# uINS.net
KiCad netlist of a schematic drawn in Altium Designer
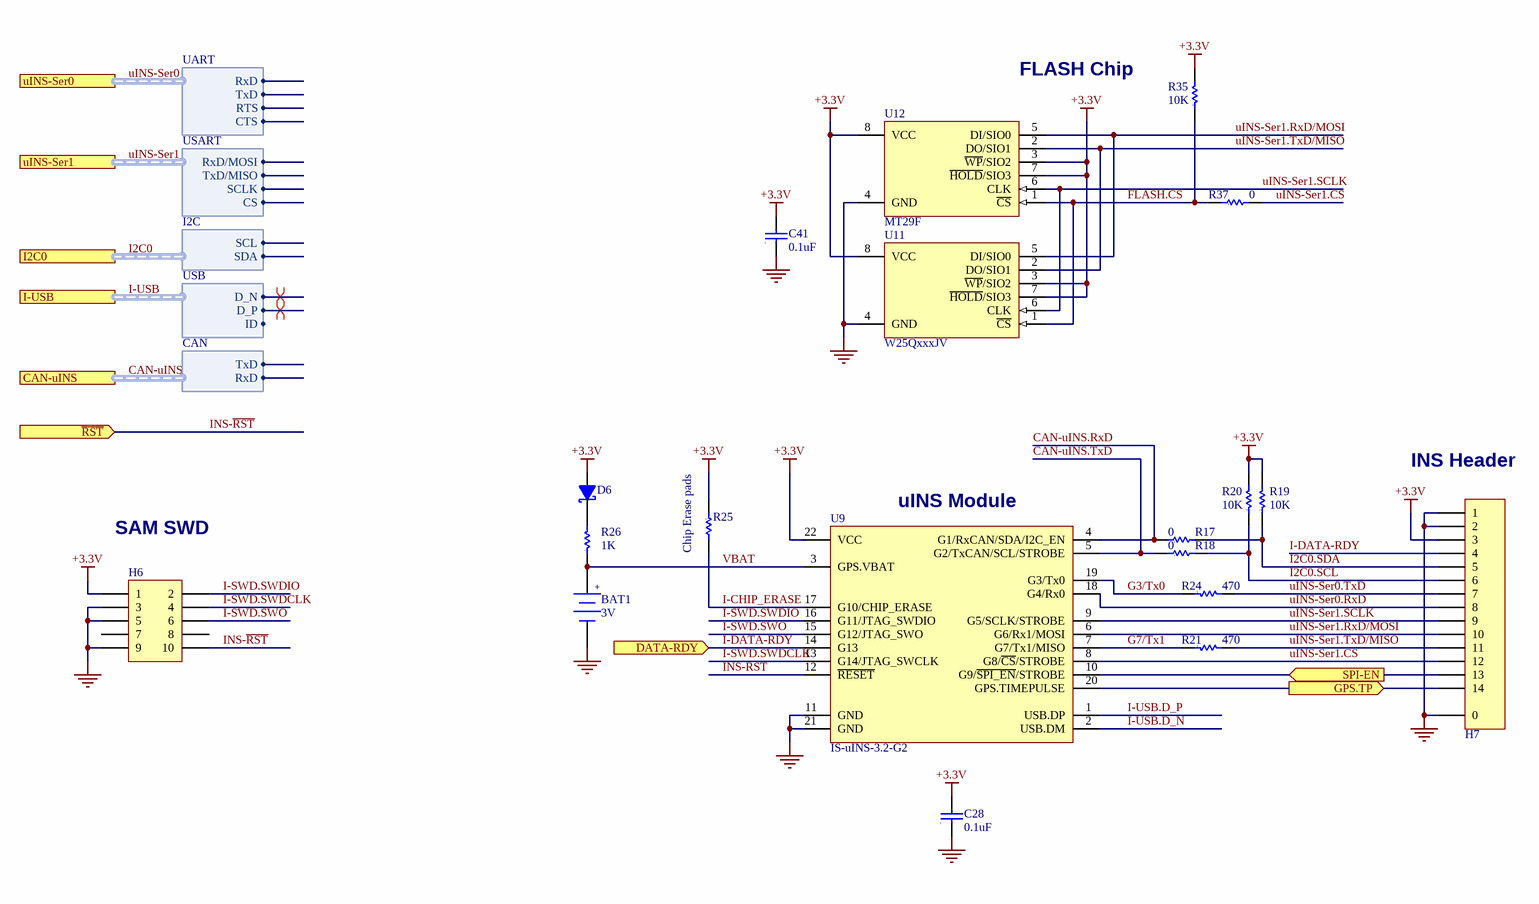
[diagram p0: uINS.SchDoc]

(export (version "E")
  (design (tool "Eeschema 10.0.6"))
  (components
    (comp (ref "BAT1")
      (value "Battery")
      (footprint "ML614S")
      (description "BATTERY LITH 3V 3MAH COIN 6.8MM")
      (fields (field (name "VOLTAGE RATING") "3V"))
      (libsource (lib "General") (part "Battery"))
    )
    (comp (ref "C28")
      (value "0.1uF")
      (footprint "0402")
      (description "CAP CER .10UF 50V X7R 10% 0402")
      (fields
        (field (name "MANUFACTURER") "TDK Corporation")
        (field (name "MANUFACTURER PART NUMBER") "C1005X7R1H104K")
        (field (name "PUBLISHER") "Altium Limited")
      )
      (libsource (lib "General") (part "Cap"))
    )
    (comp (ref "C41")
      (value "0.1uF")
      (footprint "0402")
      (description "CAP CER .10UF 50V X7R 10% 0402")
      (fields
        (field (name "MANUFACTURER") "TDK Corporation")
        (field (name "MANUFACTURER PART NUMBER") "C1005X7R1H104K")
        (field (name "PUBLISHER") "Altium Limited")
      )
      (libsource (lib "General") (part "Cap"))
    )
    (comp (ref "D6")
      (value "Diode - Schottky")
      (footprint "D0603B")
      (description "DIODE SCHOTTKY 30V 2A 0603")
      (fields
        (field (name "MANUFACTURER") "Vishay")
        (field (name "MANUFACTURER PART NUMBER") "VSKY20301608-G4-08")
      )
      (libsource (lib "General") (part "Diode - Schottky"))
    )
    (comp (ref "H6")
      (value "Hdr - 5x2pin")
      (footprint "FTSH-105-01-L-DV-K-A-P")
      (description "CONN HEADER 10POS DUAL .05\" SMD")
      (fields
        (field (name "MANUFACTURER") "Samtec")
        (field (name "MANUFACTURER PART NUMBER") "FTSH-105-01-L-DV-K-A-P")
      )
      (libsource (lib "Connectors") (part "Hdr - 5x2pin"))
    )
    (comp (ref "H7")
      (value "Hdr - 14pin - mount")
      (footprint "SM14B-GHS-TB(LF)(SN)")
      (description "CONN HEADER GH SIDE 14POS 1.25MM")
      (fields
        (field (name "MANUFACTURER") "JST")
        (field (name "MANUFACTURER PART NUMBER") "SM14B-GHS-TB(LF)(SN)")
      )
      (libsource (lib "Connectors") (part "Hdr - 14pin - mount"))
    )
    (comp (ref "R17")
      (value "0")
      (footprint "R0402")
      (description "RES SMD 0 OHM JUMPER 1/16W 0402")
      (fields
        (field (name "MANUFACTURER") "Yageo")
        (field (name "MANUFACTURER PART NUMBER") "RC0402JR-070RL")
      )
      (libsource (lib "") (part "Res_1"))
    )
    (comp (ref "R18")
      (value "0")
      (footprint "R0402")
      (description "RES SMD 0 OHM JUMPER 1/16W 0402")
      (fields
        (field (name "MANUFACTURER") "Yageo")
        (field (name "MANUFACTURER PART NUMBER") "RC0402JR-070RL")
      )
      (libsource (lib "") (part "Res_1"))
    )
    (comp (ref "R19")
      (value "10K")
      (footprint "R0402")
      (description "RES 10K OHM 1/16W 1% 0402 SMD")
      (fields
        (field (name "MANUFACTURER") "Panasonic")
        (field (name "MANUFACTURER PART NUMBER") "ERJ-2RKF1002X")
      )
      (libsource (lib "") (part "Res_2"))
    )
    (comp (ref "R20")
      (value "10K")
      (footprint "R0402")
      (description "RES 10K OHM 1/16W 1% 0402 SMD")
      (fields
        (field (name "MANUFACTURER") "Panasonic")
        (field (name "MANUFACTURER PART NUMBER") "ERJ-2RKF1002X")
      )
      (libsource (lib "") (part "Res_2"))
    )
    (comp (ref "R21")
      (value "470")
      (footprint "R0402")
      (description "RES 470 OHM 1/16W 1% 0402 SMD")
      (fields
        (field (name "MANUFACTURER") "Vishay Dale")
        (field (name "MANUFACTURER PART NUMBER") "CRCW0402470RFKED")
      )
      (libsource (lib "General") (part "Res"))
    )
    (comp (ref "R24")
      (value "470")
      (footprint "R0402")
      (description "RES 470 OHM 1/16W 1% 0402 SMD")
      (fields
        (field (name "MANUFACTURER") "Vishay Dale")
        (field (name "MANUFACTURER PART NUMBER") "CRCW0402470RFKED")
      )
      (libsource (lib "General") (part "Res"))
    )
    (comp (ref "R25")
      (value "Res")
      (footprint "R0402")
      (description "RES SMD 0402 NO LOAD")
      (libsource (lib "") (part "Res_1"))
    )
    (comp (ref "R26")
      (value "1K")
      (footprint "R0402")
      (description "RES 1.00K OHM 1/16W 1% 0402 SMD")
      (fields
        (field (name "MANUFACTURER") "Yageo")
        (field (name "MANUFACTURER PART NUMBER") "RC0402FR-071KL")
      )
      (libsource (lib "") (part "Res_2"))
    )
    (comp (ref "R35")
      (value "10K")
      (footprint "R0402")
      (description "RES 10K OHM 1/16W 1% 0402 SMD")
      (fields
        (field (name "MANUFACTURER") "Panasonic")
        (field (name "MANUFACTURER PART NUMBER") "ERJ-2RKF1002X")
      )
      (libsource (lib "") (part "Res_2"))
    )
    (comp (ref "R37")
      (value "0")
      (footprint "R0402")
      (description "RES SMD 0 OHM JUMPER 1/16W 0402")
      (fields
        (field (name "MANUFACTURER") "Yageo")
        (field (name "MANUFACTURER PART NUMBER") "RC0402JR-070RL")
      )
      (libsource (lib "") (part "Res_1"))
    )
    (comp (ref "U9")
      (value "uINS")
      (footprint "IS-uINS-3.2_no_paste")
      (description "Inertial Sense uINS")
      (fields
        (field (name "MANUFACTURER") "Inertial Sense")
        (field (name "MANUFACTURER PART NUMBER") "IS-uINS-3.2-G2")
      )
      (libsource (lib "InertialSense") (part "IS-uINS-3.2"))
    )
    (comp (ref "U11")
      (value "W25QxxxJV")
      (footprint "SOIC127P790X216-8N")
      (description "IC FLASH 128M SPI 133MHZ 8SOIC")
      (fields
        (field (name "MANUFACTURER") "Winbond")
        (field (name "MANUFACTURER PART NUMBER") "W25Q128JVSIQTR")
      )
      (libsource (lib "ICs") (part "W25Q128JV"))
    )
    (comp (ref "U12")
      (value "MT29F")
      (footprint "DFN800X600X65-8N")
      (description "IC FLASH 1G/2G SPI 8UPDFN")
      (fields
        (field (name "MANUFACTURER") "Micron Technology")
        (field (name "MANUFACTURER PART NUMBER") "MT29F2G01ABAGDWB-IT:GTR")
      )
      (libsource (lib "ICs") (part "MT29F"))
    )
  )
  (nets
    (net (code "6") (name "+3.3V") (class "Default")
      (node (ref "C28") (pin "2") (pinfunction "2_2") (pintype "passive"))
      (node (ref "C41") (pin "2") (pinfunction "2_2") (pintype "passive"))
      (node (ref "D6") (pin "A") (pinfunction "A_A") (pintype "passive"))
      (node (ref "H6") (pin "1") (pinfunction "1_1") (pintype "passive"))
      (node (ref "H7") (pin "3") (pinfunction "3_3") (pintype "passive"))
      (node (ref "R19") (pin "2") (pinfunction "2_2") (pintype "passive"))
      (node (ref "R20") (pin "2") (pinfunction "2_2") (pintype "passive"))
      (node (ref "R25") (pin "1") (pinfunction "1_1") (pintype "passive"))
      (node (ref "R35") (pin "2") (pinfunction "2_2") (pintype "passive"))
      (node (ref "U11") (pin "3") (pinfunction "~{WP}/SIO2_3") (pintype "passive"))
      (node (ref "U11") (pin "7") (pinfunction "~{HOLD}/SIO3_7") (pintype "passive"))
      (node (ref "U11") (pin "8") (pinfunction "VCC_8") (pintype "power_in"))
      (node (ref "U12") (pin "3") (pinfunction "~{WP}/SIO2_3") (pintype "passive"))
      (node (ref "U12") (pin "7") (pinfunction "~{HOLD}/SIO3_7") (pintype "passive"))
      (node (ref "U12") (pin "8") (pinfunction "VCC_8") (pintype "power_in"))
      (node (ref "U9") (pin "22") (pinfunction "VCC_22") (pintype "power_in"))
    )
    (net (code "7") (name "/CAN-uINS.RxD") (class "Default")
      (node (ref "R17") (pin "1") (pinfunction "1_1") (pintype "passive"))
      (node (ref "U9") (pin "4") (pinfunction "G1/RxCAN/SDA/I2C_EN_4") (pintype "passive"))
    )
    (net (code "8") (name "/CAN-uINS.TxD") (class "Default")
      (node (ref "R18") (pin "1") (pinfunction "1_1") (pintype "passive"))
      (node (ref "U9") (pin "5") (pinfunction "G2/TxCAN/SCL/STROBE_5") (pintype "passive"))
    )
    (net (code "9") (name "/FLASH.CS") (class "Default")
      (node (ref "R35") (pin "1") (pinfunction "1_1") (pintype "passive"))
      (node (ref "R37") (pin "1") (pinfunction "1_1") (pintype "passive"))
      (node (ref "U11") (pin "1") (pinfunction "CS_1") (pintype "input"))
      (node (ref "U12") (pin "1") (pinfunction "CS_1") (pintype "input"))
    )
    (net (code "10") (name "/G3{slash}Tx0") (class "Default")
      (node (ref "R24") (pin "1") (pinfunction "1_1") (pintype "passive"))
      (node (ref "U9") (pin "19") (pinfunction "G3/Tx0_19") (pintype "passive"))
    )
    (net (code "11") (name "/G7{slash}Tx1") (class "Default")
      (node (ref "R21") (pin "1") (pinfunction "1_1") (pintype "passive"))
      (node (ref "U9") (pin "7") (pinfunction "G7/Tx1/MISO_7") (pintype "passive"))
    )
    (net (code "12") (name "/GPS.TP") (class "Default")
      (node (ref "H7") (pin "14") (pinfunction "14_14") (pintype "passive"))
      (node (ref "U9") (pin "20") (pinfunction "GPS.TIMEPULSE_20") (pintype "passive"))
    )
    (net (code "13") (name "/I-CHIP_ERASE") (class "Default")
      (node (ref "R25") (pin "2") (pinfunction "2_2") (pintype "passive"))
      (node (ref "U9") (pin "17") (pinfunction "G10/CHIP_ERASE_17") (pintype "passive"))
    )
    (net (code "14") (name "/I-DATA-RDY") (class "Default")
      (node (ref "H7") (pin "4") (pinfunction "4_4") (pintype "passive"))
      (node (ref "U9") (pin "14") (pinfunction "G13_14") (pintype "passive"))
    )
    (net (code "15") (name "/I-SWD.SWDCLK") (class "Default")
      (node (ref "H6") (pin "4") (pinfunction "4_4") (pintype "passive"))
      (node (ref "U9") (pin "13") (pinfunction "G14/JTAG_SWCLK_13") (pintype "passive"))
    )
    (net (code "16") (name "/I-SWD.SWDIO") (class "Default")
      (node (ref "H6") (pin "2") (pinfunction "2_2") (pintype "passive"))
      (node (ref "U9") (pin "16") (pinfunction "G11/JTAG_SWDIO_16") (pintype "passive"))
    )
    (net (code "17") (name "/I-SWD.SWO") (class "Default")
      (node (ref "H6") (pin "6") (pinfunction "6_6") (pintype "passive"))
      (node (ref "U9") (pin "15") (pinfunction "G12/JTAG_SWO_15") (pintype "passive"))
    )
    (net (code "18") (name "/I-USB.D_N") (class "Default")
      (node (ref "U9") (pin "2") (pinfunction "USB.DM_2") (pintype "passive"))
    )
    (net (code "19") (name "/I-USB.D_P") (class "Default")
      (node (ref "U9") (pin "1") (pinfunction "USB.DP_1") (pintype "passive"))
    )
    (net (code "21") (name "/I2C0.SCL") (class "Default")
      (node (ref "H7") (pin "6") (pinfunction "6_6") (pintype "passive"))
      (node (ref "R18") (pin "2") (pinfunction "2_2") (pintype "passive"))
      (node (ref "R20") (pin "1") (pinfunction "1_1") (pintype "passive"))
    )
    (net (code "22") (name "/I2C0.SDA") (class "Default")
      (node (ref "H7") (pin "5") (pinfunction "5_5") (pintype "passive"))
      (node (ref "R17") (pin "2") (pinfunction "2_2") (pintype "passive"))
      (node (ref "R19") (pin "1") (pinfunction "1_1") (pintype "passive"))
    )
    (net (code "24") (name "/INS-~{RST}") (class "Default")
      (node (ref "H6") (pin "10") (pinfunction "10_10") (pintype "passive"))
      (node (ref "U9") (pin "12") (pinfunction "~{RESET}_12") (pintype "passive"))
    )
    (net (code "25") (name "/SPI-EN") (class "Default")
      (node (ref "H7") (pin "13") (pinfunction "13_13") (pintype "passive"))
      (node (ref "U9") (pin "10") (pinfunction "G9/~{SPI_EN}/STROBE_10") (pintype "passive"))
    )
    (net (code "26") (name "/VBAT") (class "Default")
      (node (ref "BAT1") (pin "+") (pinfunction "+_+") (pintype "passive"))
      (node (ref "R26") (pin "1") (pinfunction "1_1") (pintype "passive"))
      (node (ref "U9") (pin "3") (pinfunction "GPS.VBAT_3") (pintype "passive"))
    )
    (net (code "27") (name "/uINS-Ser0.RxD") (class "Default")
      (node (ref "H7") (pin "8") (pinfunction "8_8") (pintype "passive"))
      (node (ref "U9") (pin "18") (pinfunction "G4/Rx0_18") (pintype "passive"))
    )
    (net (code "28") (name "/uINS-Ser0.TxD") (class "Default")
      (node (ref "H7") (pin "7") (pinfunction "7_7") (pintype "passive"))
      (node (ref "R24") (pin "2") (pinfunction "2_2") (pintype "passive"))
    )
    (net (code "30") (name "/uINS-Ser1.CS") (class "Default")
      (node (ref "H7") (pin "12") (pinfunction "12_12") (pintype "passive"))
      (node (ref "R37") (pin "2") (pinfunction "2_2") (pintype "passive"))
      (node (ref "U9") (pin "8") (pinfunction "G8/~{CS}/STROBE_8") (pintype "passive"))
    )
    (net (code "31") (name "/uINS-Ser1.RxD{slash}MOSI") (class "Default")
      (node (ref "H7") (pin "10") (pinfunction "10_10") (pintype "passive"))
      (node (ref "U11") (pin "5") (pinfunction "DI/SIO0_5") (pintype "passive"))
      (node (ref "U12") (pin "5") (pinfunction "DI/SIO0_5") (pintype "passive"))
      (node (ref "U9") (pin "6") (pinfunction "G6/Rx1/MOSI_6") (pintype "passive"))
    )
    (net (code "32") (name "/uINS-Ser1.SCLK") (class "Default")
      (node (ref "H7") (pin "9") (pinfunction "9_9") (pintype "passive"))
      (node (ref "U11") (pin "6") (pinfunction "CLK_6") (pintype "input"))
      (node (ref "U12") (pin "6") (pinfunction "CLK_6") (pintype "input"))
      (node (ref "U9") (pin "9") (pinfunction "G5/SCLK/STROBE_9") (pintype "passive"))
    )
    (net (code "33") (name "/uINS-Ser1.TxD{slash}MISO") (class "Default")
      (node (ref "H7") (pin "11") (pinfunction "11_11") (pintype "passive"))
      (node (ref "R21") (pin "2") (pinfunction "2_2") (pintype "passive"))
      (node (ref "U11") (pin "2") (pinfunction "DO/SIO1_2") (pintype "passive"))
      (node (ref "U12") (pin "2") (pinfunction "DO/SIO1_2") (pintype "passive"))
    )
    (net (code "36") (name "GND") (class "Default")
      (node (ref "BAT1") (pin "-") (pinfunction "-_-") (pintype "passive"))
      (node (ref "C28") (pin "1") (pinfunction "1_1") (pintype "passive"))
      (node (ref "C41") (pin "1") (pinfunction "1_1") (pintype "passive"))
      (node (ref "H6") (pin "3") (pinfunction "3_3") (pintype "passive"))
      (node (ref "H6") (pin "5") (pinfunction "5_5") (pintype "passive"))
      (node (ref "H6") (pin "9") (pinfunction "9_9") (pintype "passive"))
      (node (ref "H7") (pin "0") (pinfunction "0_0") (pintype "passive"))
      (node (ref "H7") (pin "1") (pinfunction "1_1") (pintype "passive"))
      (node (ref "H7") (pin "2") (pinfunction "2_2") (pintype "passive"))
      (node (ref "U11") (pin "4") (pinfunction "GND_4") (pintype "power_in"))
      (node (ref "U12") (pin "4") (pinfunction "GND_4") (pintype "power_in"))
      (node (ref "U9") (pin "11") (pinfunction "GND_11") (pintype "power_in"))
      (node (ref "U9") (pin "21") (pinfunction "GND_21") (pintype "power_in"))
    )
    (net (code "37") (name "Net-(D6-PadC)") (class "Default")
      (node (ref "D6") (pin "C") (pinfunction "C_C") (pintype "passive"))
      (node (ref "R26") (pin "2") (pinfunction "2_2") (pintype "passive"))
    )
    (net (code "38") (name "unconnected-(H6-Pad7)") (class "Default")
      (node (ref "H6") (pin "7") (pinfunction "7_7") (pintype "passive"))
    )
    (net (code "39") (name "unconnected-(H6-Pad8)") (class "Default")
      (node (ref "H6") (pin "8") (pinfunction "8_8") (pintype "passive"))
    )
  )
)
